# sensor_v3a.net
KiCad netlist of a schematic drawn in EAGLE
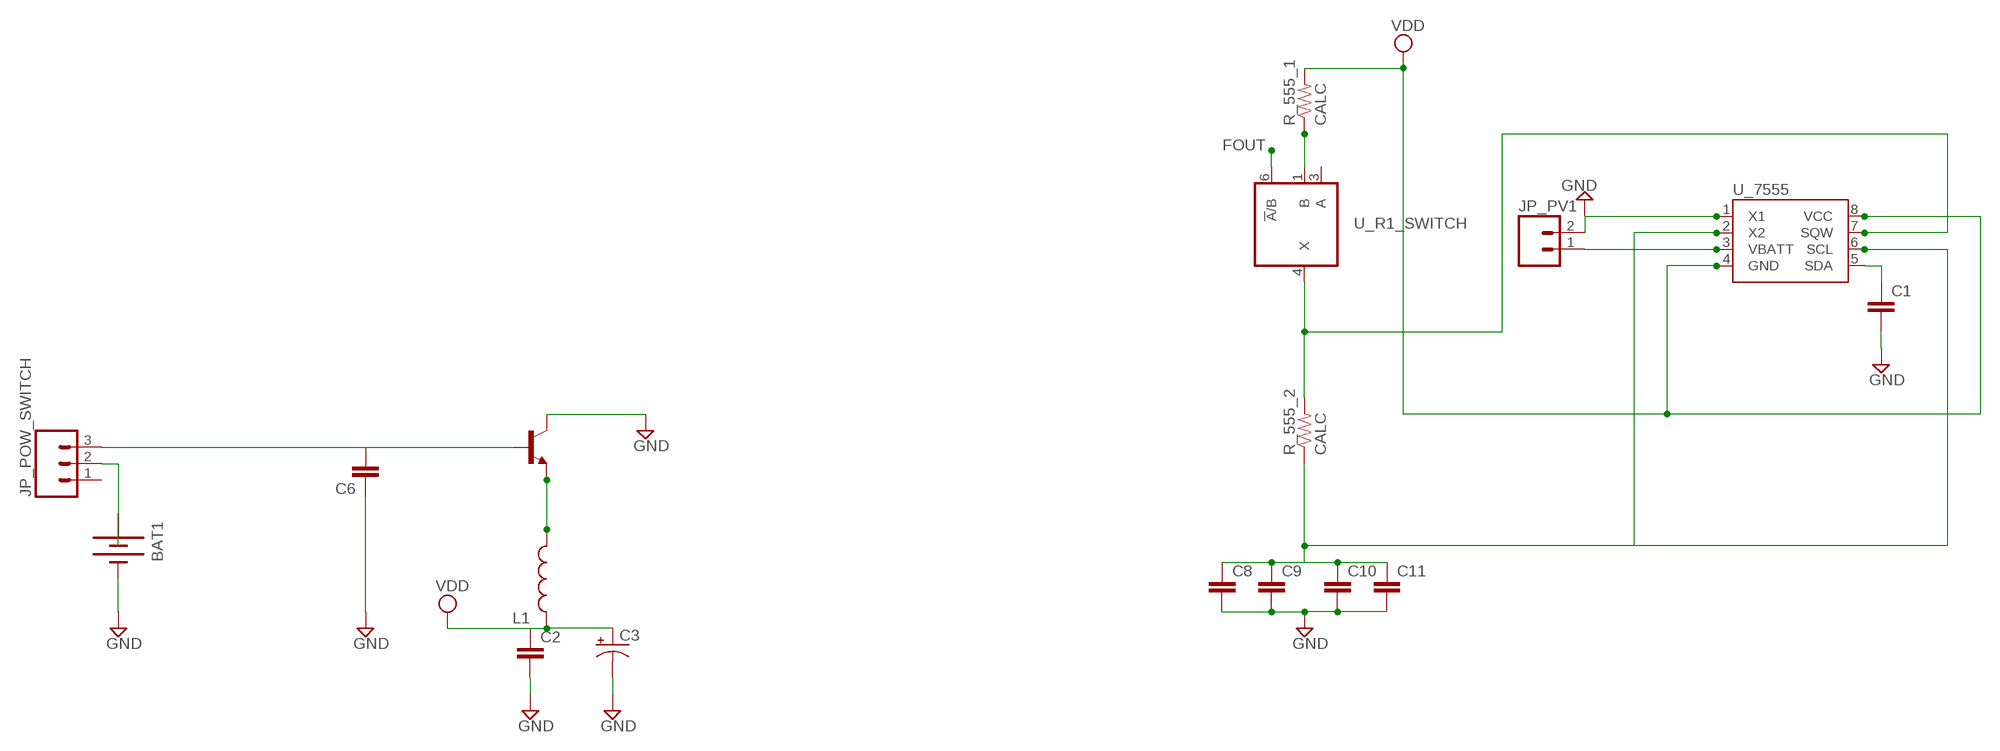
[diagram p0: schematic, sheet 1]

(export (version "E")
  (design (tool "Eeschema 10.0.6"))
  (components
    (comp (ref "BAT1")
      (value "BATTERY20PTH_LAB")
      (footprint "eagle-import:BATTCOM_20MM_PTH")
      (libsource (lib "eagle-import") (part "BATTERY20PTH_LAB"))
    )
    (comp (ref "C1")
      (value "CAP0603-CAP")
      (footprint "eagle-import:0603-CAP")
      (libsource (lib "eagle-import") (part "SparkFun-Capacitors_CAP0603-CAP"))
    )
    (comp (ref "C2")
      (value "CAP0603-CAP")
      (footprint "eagle-import:0603-CAP")
      (libsource (lib "eagle-import") (part "SparkFun-Capacitors_CAP0603-CAP"))
    )
    (comp (ref "C3")
      (value "CAP_POL1206")
      (footprint "eagle-import:EIA3216")
      (libsource (lib "eagle-import") (part "CAP_POL1206"))
    )
    (comp (ref "C6")
      (value "CAP0603-CAP")
      (footprint "eagle-import:0603-CAP")
      (libsource (lib "eagle-import") (part "SparkFun-Capacitors_CAP0603-CAP"))
    )
    (comp (ref "C8")
      (value "CAP0805")
      (footprint "eagle-import:0805")
      (libsource (lib "eagle-import") (part "CAP0805"))
    )
    (comp (ref "C9")
      (value "CAP0805")
      (footprint "eagle-import:0805")
      (libsource (lib "eagle-import") (part "CAP0805"))
    )
    (comp (ref "C10")
      (value "CAP0805")
      (footprint "eagle-import:0805")
      (libsource (lib "eagle-import") (part "CAP0805"))
    )
    (comp (ref "C11")
      (value "CAP0805")
      (footprint "eagle-import:0805")
      (libsource (lib "eagle-import") (part "CAP0805"))
    )
    (comp (ref "JP_POW_SWITCH")
      (value "M03LOCK")
      (footprint "eagle-import:1X03_LOCK")
      (libsource (lib "eagle-import") (part "M03LOCK"))
    )
    (comp (ref "JP_PV1")
      (value "M02LOCK")
      (footprint "eagle-import:1X02_LOCK")
      (libsource (lib "eagle-import") (part "M02LOCK"))
    )
    (comp (ref "L1")
      (value "INDUCTOR0603")
      (footprint "eagle-import:0603")
      (libsource (lib "eagle-import") (part "INDUCTOR0603"))
    )
    (comp (ref "R_555_1")
      (value "CALC")
      (footprint "eagle-import:0805")
      (libsource (lib "eagle-import") (part "RESISTOR0805-RES"))
    )
    (comp (ref "R_555_2")
      (value "CALC")
      (footprint "eagle-import:0805")
      (libsource (lib "eagle-import") (part "RESISTOR0805-RES"))
    )
    (comp (ref "U_7555")
      (value "DS1307SO8")
      (footprint "eagle-import:SO08")
      (libsource (lib "eagle-import") (part "DS1307SO8"))
    )
    (comp (ref "U_R1_SWITCH")
      (value "741G3157DCKR")
      (footprint "eagle-import:DCK_R-PDSO-G6")
      (libsource (lib "eagle-import") (part "741G3157DCKR"))
    )
    (comp (ref "U_VREF")
      (value "TRANSISTOR_NPNSOT23-3")
      (footprint "eagle-import:SOT23-3")
      (libsource (lib "eagle-import") (part "TRANSISTOR_NPNSOT23-3"))
    )
  )
  (nets
    (net (code "1") (name "/FOUT") (class "Default")
      (node (ref "JP_PV1") (pin "1") (pinfunction "1_1") (pintype "passive"))
      (node (ref "U_7555") (pin "3") (pinfunction "VBATT_3") (pintype "bidirectional"))
      (node (ref "U_R1_SWITCH") (pin "6") (pinfunction "~{A}/B_6") (pintype "input"))
    )
    (net (code "2") (name "/P2") (class "Default")
      (node (ref "C10") (pin "1") (pinfunction "1_1") (pintype "passive"))
      (node (ref "C11") (pin "1") (pinfunction "1_1") (pintype "passive"))
      (node (ref "C8") (pin "1") (pinfunction "1_1") (pintype "passive"))
      (node (ref "C9") (pin "1") (pinfunction "1_1") (pintype "passive"))
      (node (ref "R_555_2") (pin "1") (pinfunction "1_1") (pintype "passive"))
      (node (ref "U_7555") (pin "2") (pinfunction "X2_2") (pintype "bidirectional"))
      (node (ref "U_7555") (pin "6") (pinfunction "SCL_6") (pintype "bidirectional"))
    )
    (net (code "3") (name "GND") (class "Default")
      (node (ref "BAT1") (pin "2") (pinfunction "-_2") (pintype "power_in"))
      (node (ref "C1") (pin "2") (pinfunction "2_2") (pintype "passive"))
      (node (ref "C10") (pin "2") (pinfunction "2_2") (pintype "passive"))
      (node (ref "C11") (pin "2") (pinfunction "2_2") (pintype "passive"))
      (node (ref "C2") (pin "2") (pinfunction "2_2") (pintype "passive"))
      (node (ref "C3") (pin "C") (pinfunction "-_C") (pintype "passive"))
      (node (ref "C6") (pin "1") (pinfunction "1_1") (pintype "passive"))
      (node (ref "C8") (pin "2") (pinfunction "2_2") (pintype "passive"))
      (node (ref "C9") (pin "2") (pinfunction "2_2") (pintype "passive"))
      (node (ref "JP_PV1") (pin "2") (pinfunction "2_2") (pintype "passive"))
      (node (ref "U_7555") (pin "1") (pinfunction "X1_1") (pintype "bidirectional"))
      (node (ref "U_VREF") (pin "3") (pinfunction "C_3") (pintype "passive"))
    )
    (net (code "4") (name "Net-(BAT1-+)") (class "Default")
      (node (ref "BAT1") (pin "1") (pinfunction "+_1") (pintype "power_in"))
      (node (ref "JP_POW_SWITCH") (pin "2") (pinfunction "2_2") (pintype "passive"))
    )
    (net (code "5") (name "Net-(U_7555-SDA)") (class "Default")
      (node (ref "C1") (pin "1") (pinfunction "1_1") (pintype "passive"))
      (node (ref "U_7555") (pin "5") (pinfunction "SDA_5") (pintype "bidirectional"))
    )
    (net (code "6") (name "Net-(U_7555-SQW)") (class "Default")
      (node (ref "R_555_2") (pin "2") (pinfunction "2_2") (pintype "passive"))
      (node (ref "U_7555") (pin "7") (pinfunction "SQW_7") (pintype "bidirectional"))
      (node (ref "U_R1_SWITCH") (pin "4") (pinfunction "X_4") (pintype "bidirectional"))
    )
    (net (code "7") (name "Net-(U_R1_SWITCHA-B)") (class "Default")
      (node (ref "R_555_1") (pin "1") (pinfunction "1_1") (pintype "passive"))
      (node (ref "U_R1_SWITCH") (pin "1") (pinfunction "B_1") (pintype "bidirectional"))
    )
    (net (code "8") (name "Net-(U_VREF-B)") (class "Default")
      (node (ref "C6") (pin "2") (pinfunction "2_2") (pintype "passive"))
      (node (ref "JP_POW_SWITCH") (pin "3") (pinfunction "3_3") (pintype "passive"))
      (node (ref "U_VREF") (pin "1") (pinfunction "B_1") (pintype "passive"))
    )
    (net (code "9") (name "Net-(U_VREF-E)") (class "Default")
      (node (ref "L1") (pin "2") (pinfunction "2_2") (pintype "passive"))
      (node (ref "U_VREF") (pin "2") (pinfunction "E_2") (pintype "passive"))
    )
    (net (code "10") (name "VDD") (class "Default")
      (node (ref "C2") (pin "1") (pinfunction "1_1") (pintype "passive"))
      (node (ref "C3") (pin "A") (pinfunction "+_A") (pintype "passive"))
      (node (ref "L1") (pin "1") (pinfunction "1_1") (pintype "passive"))
      (node (ref "R_555_1") (pin "2") (pinfunction "2_2") (pintype "passive"))
      (node (ref "U_7555") (pin "4") (pinfunction "GND_4") (pintype "bidirectional"))
      (node (ref "U_7555") (pin "8") (pinfunction "VCC_8") (pintype "bidirectional"))
    )
    (net (code "11") (name "unconnected-(JP_POW_SWITCH-Pad1)") (class "Default")
      (node (ref "JP_POW_SWITCH") (pin "1") (pinfunction "1_1") (pintype "passive"))
    )
    (net (code "12") (name "unconnected-(U_R1_SWITCHA-A-Pad3)") (class "Default")
      (node (ref "U_R1_SWITCH") (pin "3") (pinfunction "A_3") (pintype "bidirectional"))
    )
  )
)
